# EMS_esp32_wifi.net
KiCad netlist of a schematic drawn in EAGLE
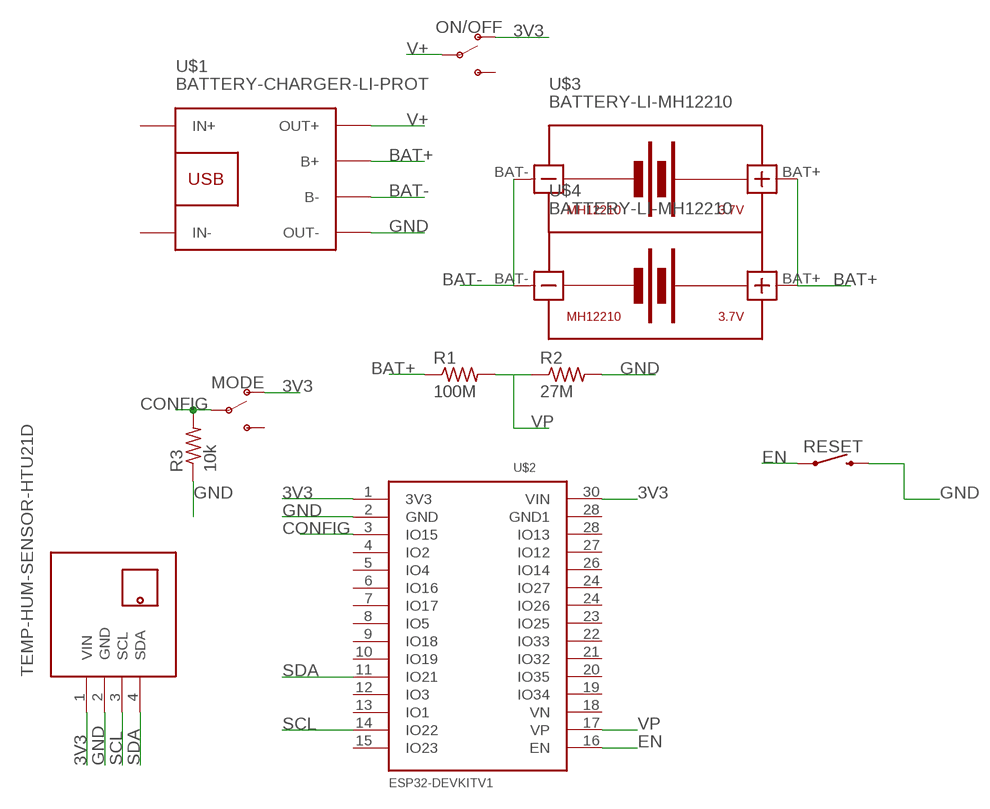
[diagram p0: schematic, sheet 1]

(export (version "E")
  (design (tool "Eeschema 10.0.6"))
  (components
    (comp (ref "MODE")
      (value "SWITCH-SPDT-PTH-11.6X4.0MM")
      (footprint "eagle-import:SWITCH_SPDT_PTH_11.6X4.0MM")
      (libsource (lib "eagle-import") (part "SWITCH-SPDT-PTH-11.6X4.0MM"))
    )
    (comp (ref "ON/OFF")
      (value "SWITCH-SPDT-PTH-11.6X4.0MM")
      (footprint "eagle-import:SWITCH_SPDT_PTH_11.6X4.0MM")
      (libsource (lib "eagle-import") (part "SWITCH-SPDT-PTH-11.6X4.0MM"))
    )
    (comp (ref "R1")
      (value "100M")
      (footprint "eagle-import:0204_7")
      (libsource (lib "eagle-import") (part "R-US_0204/7"))
    )
    (comp (ref "R2")
      (value "27M")
      (footprint "eagle-import:0204_7")
      (libsource (lib "eagle-import") (part "R-US_0204/7"))
    )
    (comp (ref "R3")
      (value "10k")
      (footprint "eagle-import:0204_7")
      (libsource (lib "eagle-import") (part "R-US_0204/7"))
    )
    (comp (ref "RESET")
      (value "MOMENTARY-SWITCH-SPST-PTH-6.0MM")
      (footprint "eagle-import:TACTILE_SWITCH_PTH_6.0MM")
      (libsource (lib "eagle-import") (part "MOMENTARY-SWITCH-SPST-PTH-6.0MM"))
    )
    (comp (ref "U$1")
      (value "BATTERY-CHARGER-LI-PROT")
      (footprint "eagle-import:BATTERY-CHARGER-LI-PROT")
      (libsource (lib "eagle-import") (part "BATTERY-CHARGER-LI-PROT"))
    )
    (comp (ref "U$2")
      (value "ESP32DEVKITV1")
      (footprint "eagle-import:ESP32-DEVKITV1")
      (libsource (lib "eagle-import") (part "ESP32DEVKITV1"))
    )
    (comp (ref "U$3")
      (value "BATTERY-LI-MH12210")
      (footprint "eagle-import:BATTERY-LI-MH12210")
      (libsource (lib "eagle-import") (part "BATTERY-LI-MH12210"))
    )
    (comp (ref "U$4")
      (value "BATTERY-LI-MH12210")
      (footprint "eagle-import:BATTERY-LI-MH12210")
      (libsource (lib "eagle-import") (part "BATTERY-LI-MH12210"))
    )
    (comp (ref "U$6")
      (value "TEMP-HUM-SENSOR-HTU21D")
      (footprint "eagle-import:TEMP-HUM-SENSOR-HTU21D")
      (libsource (lib "eagle-import") (part "TEMP-HUM-SENSOR-HTU21D"))
    )
  )
  (nets
    (net (code "1") (name "/3V3") (class "Default")
      (node (ref "MODE") (pin "1") (pinfunction "O_1") (pintype "passive"))
      (node (ref "ON/OFF") (pin "1") (pinfunction "O_1") (pintype "passive"))
      (node (ref "U$2") (pin "1") (pinfunction "3V3_1") (pintype "bidirectional"))
      (node (ref "U$2") (pin "30") (pinfunction "VIN_30") (pintype "bidirectional"))
      (node (ref "U$6") (pin "1") (pinfunction "VIN_1") (pintype "power_in"))
    )
    (net (code "2") (name "/BAT+") (class "Default")
      (node (ref "R1") (pin "1") (pinfunction "1_1") (pintype "passive"))
      (node (ref "U$1") (pin "B+") (pinfunction "B+_B+") (pintype "bidirectional"))
      (node (ref "U$3") (pin "BAT+") (pinfunction "BAT+_BAT+") (pintype "power_in"))
      (node (ref "U$4") (pin "BAT+") (pinfunction "BAT+_BAT+") (pintype "power_in"))
    )
    (net (code "3") (name "/BAT-") (class "Default")
      (node (ref "U$1") (pin "B-") (pinfunction "B-_B-") (pintype "bidirectional"))
      (node (ref "U$3") (pin "BAT-") (pinfunction "BAT-_BAT-") (pintype "power_in"))
      (node (ref "U$4") (pin "BAT-") (pinfunction "BAT-_BAT-") (pintype "power_in"))
    )
    (net (code "4") (name "/CONFIG") (class "Default")
      (node (ref "MODE") (pin "2") (pinfunction "P_2") (pintype "passive"))
      (node (ref "R3") (pin "2") (pinfunction "2_2") (pintype "passive"))
      (node (ref "U$2") (pin "3") (pinfunction "IO15_3") (pintype "bidirectional"))
    )
    (net (code "5") (name "/EN") (class "Default")
      (node (ref "RESET") (pin "1") (pinfunction "1_1") (pintype "passive"))
      (node (ref "U$2") (pin "16") (pinfunction "EN_16") (pintype "bidirectional"))
    )
    (net (code "6") (name "/GND") (class "Default")
      (node (ref "R2") (pin "2") (pinfunction "2_2") (pintype "passive"))
      (node (ref "R3") (pin "1") (pinfunction "1_1") (pintype "passive"))
      (node (ref "RESET") (pin "3") (pinfunction "2_3") (pintype "passive"))
      (node (ref "U$1") (pin "OUT-") (pinfunction "OUT-_OUT-") (pintype "bidirectional"))
      (node (ref "U$2") (pin "2") (pinfunction "GND_2") (pintype "bidirectional"))
      (node (ref "U$6") (pin "2") (pinfunction "GND_2") (pintype "power_in"))
    )
    (net (code "7") (name "/SCL") (class "Default")
      (node (ref "U$2") (pin "14") (pinfunction "IO22_14") (pintype "bidirectional"))
      (node (ref "U$6") (pin "3") (pinfunction "SCL_3") (pintype "bidirectional"))
    )
    (net (code "8") (name "/SDA") (class "Default")
      (node (ref "U$2") (pin "11") (pinfunction "IO21_11") (pintype "bidirectional"))
      (node (ref "U$6") (pin "4") (pinfunction "SDA_4") (pintype "bidirectional"))
    )
    (net (code "9") (name "/V+") (class "Default")
      (node (ref "ON/OFF") (pin "2") (pinfunction "P_2") (pintype "passive"))
      (node (ref "U$1") (pin "OUT+") (pinfunction "OUT+_OUT+") (pintype "bidirectional"))
    )
    (net (code "10") (name "/VP") (class "Default")
      (node (ref "R1") (pin "2") (pinfunction "2_2") (pintype "passive"))
      (node (ref "R2") (pin "1") (pinfunction "1_1") (pintype "passive"))
      (node (ref "U$2") (pin "17") (pinfunction "VP_17") (pintype "bidirectional"))
    )
    (net (code "11") (name "unconnected-(MODE-S-Pad3)") (class "Default")
      (node (ref "MODE") (pin "3") (pinfunction "S_3") (pintype "passive"))
    )
    (net (code "12") (name "unconnected-(ON/OFF-S-Pad3)") (class "Default")
      (node (ref "ON/OFF") (pin "3") (pinfunction "S_3") (pintype "passive"))
    )
    (net (code "13") (name "unconnected-(U$1-PadIN+)") (class "Default")
      (node (ref "U$1") (pin "IN+") (pinfunction "IN+_IN+") (pintype "bidirectional"))
    )
    (net (code "14") (name "unconnected-(U$1-PadIN-)") (class "Default")
      (node (ref "U$1") (pin "IN-") (pinfunction "IN-_IN-") (pintype "bidirectional"))
    )
    (net (code "15") (name "unconnected-(U$2-GND1-Pad28)") (class "Default")
      (node (ref "U$2") (pin "28") (pinfunction "GND1_28") (pintype "bidirectional"))
    )
    (net (code "16") (name "unconnected-(U$2-IO1-Pad13)") (class "Default")
      (node (ref "U$2") (pin "13") (pinfunction "IO1_13") (pintype "bidirectional"))
    )
    (net (code "17") (name "unconnected-(U$2-IO2-Pad4)") (class "Default")
      (node (ref "U$2") (pin "4") (pinfunction "IO2_4") (pintype "bidirectional"))
    )
    (net (code "18") (name "unconnected-(U$2-IO3-Pad12)") (class "Default")
      (node (ref "U$2") (pin "12") (pinfunction "IO3_12") (pintype "bidirectional"))
    )
    (net (code "19") (name "unconnected-(U$2-IO4-Pad5)") (class "Default")
      (node (ref "U$2") (pin "5") (pinfunction "IO4_5") (pintype "bidirectional"))
    )
    (net (code "20") (name "unconnected-(U$2-IO5-Pad8)") (class "Default")
      (node (ref "U$2") (pin "8") (pinfunction "IO5_8") (pintype "bidirectional"))
    )
    (net (code "21") (name "unconnected-(U$2-IO12-Pad27)") (class "Default")
      (node (ref "U$2") (pin "27") (pinfunction "IO12_27") (pintype "bidirectional"))
    )
    (net (code "22") (name "unconnected-(U$2-IO13-Pad28)") (class "Default")
      (node (ref "U$2") (pin "28") (pinfunction "IO13_28") (pintype "bidirectional"))
    )
    (net (code "23") (name "unconnected-(U$2-IO14-Pad26)") (class "Default")
      (node (ref "U$2") (pin "26") (pinfunction "IO14_26") (pintype "bidirectional"))
    )
    (net (code "24") (name "unconnected-(U$2-IO16-Pad6)") (class "Default")
      (node (ref "U$2") (pin "6") (pinfunction "IO16_6") (pintype "bidirectional"))
    )
    (net (code "25") (name "unconnected-(U$2-IO17-Pad7)") (class "Default")
      (node (ref "U$2") (pin "7") (pinfunction "IO17_7") (pintype "bidirectional"))
    )
    (net (code "26") (name "unconnected-(U$2-IO18-Pad9)") (class "Default")
      (node (ref "U$2") (pin "9") (pinfunction "IO18_9") (pintype "bidirectional"))
    )
    (net (code "27") (name "unconnected-(U$2-IO19-Pad10)") (class "Default")
      (node (ref "U$2") (pin "10") (pinfunction "IO19_10") (pintype "bidirectional"))
    )
    (net (code "28") (name "unconnected-(U$2-IO23-Pad15)") (class "Default")
      (node (ref "U$2") (pin "15") (pinfunction "IO23_15") (pintype "bidirectional"))
    )
    (net (code "29") (name "unconnected-(U$2-IO25-Pad23)") (class "Default")
      (node (ref "U$2") (pin "23") (pinfunction "IO25_23") (pintype "bidirectional"))
    )
    (net (code "30") (name "unconnected-(U$2-IO26-Pad24)") (class "Default")
      (node (ref "U$2") (pin "24") (pinfunction "IO26_24") (pintype "bidirectional"))
    )
    (net (code "31") (name "unconnected-(U$2-IO27-Pad24)") (class "Default")
      (node (ref "U$2") (pin "24") (pinfunction "IO27_24") (pintype "bidirectional"))
    )
    (net (code "32") (name "unconnected-(U$2-IO32-Pad21)") (class "Default")
      (node (ref "U$2") (pin "21") (pinfunction "IO32_21") (pintype "bidirectional"))
    )
    (net (code "33") (name "unconnected-(U$2-IO33-Pad22)") (class "Default")
      (node (ref "U$2") (pin "22") (pinfunction "IO33_22") (pintype "bidirectional"))
    )
    (net (code "34") (name "unconnected-(U$2-IO34-Pad19)") (class "Default")
      (node (ref "U$2") (pin "19") (pinfunction "IO34_19") (pintype "bidirectional"))
    )
    (net (code "35") (name "unconnected-(U$2-IO35-Pad20)") (class "Default")
      (node (ref "U$2") (pin "20") (pinfunction "IO35_20") (pintype "bidirectional"))
    )
    (net (code "36") (name "unconnected-(U$2-VN-Pad18)") (class "Default")
      (node (ref "U$2") (pin "18") (pinfunction "VN_18") (pintype "bidirectional"))
    )
  )
)
